# fr5949_v3.net
KiCad netlist of a schematic drawn in EAGLE
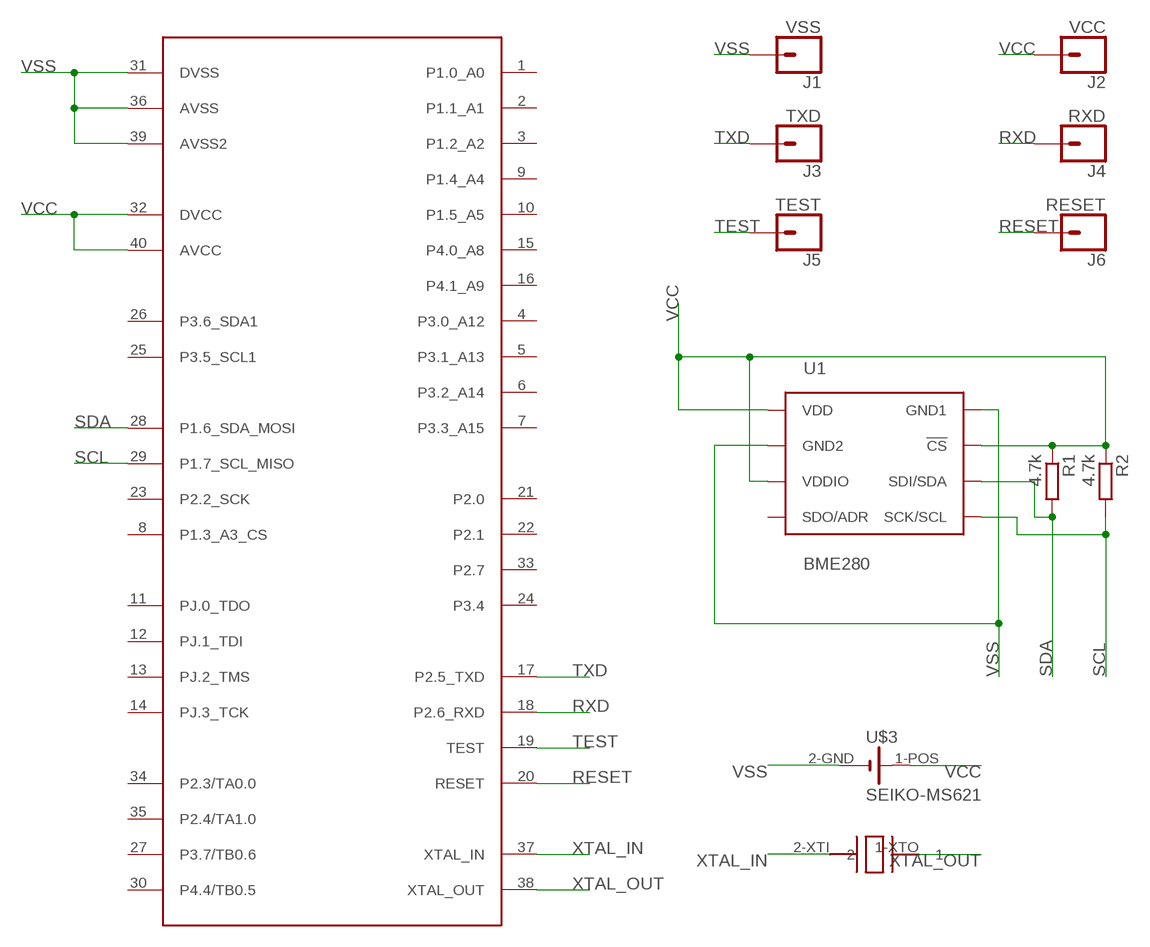
[diagram p0: schematic, sheet 1]

(export (version "E")
  (design (tool "Eeschema 10.0.6"))
  (components
    (comp (ref "J1")
      (value "VSS")
      (footprint "eagle-import:1X01")
      (libsource (lib "eagle-import") (part "CONN_01"))
    )
    (comp (ref "J2")
      (value "VCC")
      (footprint "eagle-import:1X01")
      (libsource (lib "eagle-import") (part "CONN_01"))
    )
    (comp (ref "J3")
      (value "TXD")
      (footprint "eagle-import:1X01")
      (libsource (lib "eagle-import") (part "CONN_01"))
    )
    (comp (ref "J4")
      (value "RXD")
      (footprint "eagle-import:1X01")
      (libsource (lib "eagle-import") (part "CONN_01"))
    )
    (comp (ref "J5")
      (value "TEST")
      (footprint "eagle-import:1X01")
      (libsource (lib "eagle-import") (part "CONN_01"))
    )
    (comp (ref "J6")
      (value "RESET")
      (footprint "eagle-import:1X01")
      (libsource (lib "eagle-import") (part "CONN_01"))
    )
    (comp (ref "R1")
      (value "4.7k")
      (footprint "eagle-import:R0201")
      (libsource (lib "eagle-import") (part "R-EU_R0201"))
    )
    (comp (ref "R2")
      (value "4.7k")
      (footprint "eagle-import:R0201")
      (libsource (lib "eagle-import") (part "R-EU_R0201"))
    )
    (comp (ref "U$1")
      (value "MSP430FR5949_RHA")
      (footprint "eagle-import:RHA-40-VQFN")
      (libsource (lib "eagle-import") (part "MSP430FR5949_RHA"))
    )
    (comp (ref "U$2")
      (value "ABS06")
      (footprint "eagle-import:2.0X1.0RTC")
      (libsource (lib "eagle-import") (part "ABS06"))
    )
    (comp (ref "U$3")
      (value "SEIKO-MS621")
      (footprint "eagle-import:SEIKO_MICRO")
      (libsource (lib "eagle-import") (part "SEIKO-MS621"))
    )
    (comp (ref "U1")
      (value "BME280")
      (footprint "eagle-import:BME280_LGA")
      (libsource (lib "eagle-import") (part "BME280"))
    )
  )
  (nets
    (net (code "1") (name "/RESET") (class "Default")
      (node (ref "J6") (pin "1") (pinfunction "1_1") (pintype "passive"))
      (node (ref "U$1") (pin "20") (pinfunction "RESET_20") (pintype "bidirectional"))
    )
    (net (code "2") (name "/RXD") (class "Default")
      (node (ref "J4") (pin "1") (pinfunction "1_1") (pintype "passive"))
      (node (ref "U$1") (pin "18") (pinfunction "P2.6_RXD_18") (pintype "bidirectional"))
    )
    (net (code "3") (name "/SCL") (class "Default")
      (node (ref "R2") (pin "2") (pinfunction "2_2") (pintype "passive"))
      (node (ref "U$1") (pin "29") (pinfunction "P1.7_SCL_MISO_29") (pintype "bidirectional"))
      (node (ref "U1") (pin "P$4") (pinfunction "SCK/SCL_P$4") (pintype "bidirectional"))
    )
    (net (code "4") (name "/SDA") (class "Default")
      (node (ref "R1") (pin "2") (pinfunction "2_2") (pintype "passive"))
      (node (ref "U$1") (pin "28") (pinfunction "P1.6_SDA_MOSI_28") (pintype "bidirectional"))
      (node (ref "U1") (pin "P$3") (pinfunction "SDI/SDA_P$3") (pintype "bidirectional"))
    )
    (net (code "5") (name "/TEST") (class "Default")
      (node (ref "J5") (pin "1") (pinfunction "1_1") (pintype "passive"))
      (node (ref "U$1") (pin "19") (pinfunction "TEST_19") (pintype "bidirectional"))
    )
    (net (code "6") (name "/TXD") (class "Default")
      (node (ref "J3") (pin "1") (pinfunction "1_1") (pintype "passive"))
      (node (ref "U$1") (pin "17") (pinfunction "P2.5_TXD_17") (pintype "bidirectional"))
    )
    (net (code "7") (name "/VCC") (class "Default")
      (node (ref "J2") (pin "1") (pinfunction "1_1") (pintype "passive"))
      (node (ref "R1") (pin "1") (pinfunction "1_1") (pintype "passive"))
      (node (ref "R2") (pin "1") (pinfunction "1_1") (pintype "passive"))
      (node (ref "U$1") (pin "32") (pinfunction "DVCC_32") (pintype "bidirectional"))
      (node (ref "U$1") (pin "40") (pinfunction "AVCC_40") (pintype "bidirectional"))
      (node (ref "U$3") (pin "1-POS") (pinfunction "+_1-POS") (pintype "passive"))
      (node (ref "U1") (pin "P$2") (pinfunction "~{CS}_P$2") (pintype "bidirectional"))
      (node (ref "U1") (pin "P$6") (pinfunction "VDDIO_P$6") (pintype "bidirectional"))
      (node (ref "U1") (pin "P$8") (pinfunction "VDD_P$8") (pintype "bidirectional"))
    )
    (net (code "8") (name "/VSS") (class "Default")
      (node (ref "J1") (pin "1") (pinfunction "1_1") (pintype "passive"))
      (node (ref "U$1") (pin "31") (pinfunction "DVSS_31") (pintype "bidirectional"))
      (node (ref "U$1") (pin "36") (pinfunction "AVSS_36") (pintype "bidirectional"))
      (node (ref "U$1") (pin "39") (pinfunction "AVSS2_39") (pintype "bidirectional"))
      (node (ref "U$3") (pin "2-GND") (pinfunction "-_2-GND") (pintype "passive"))
      (node (ref "U1") (pin "P$1") (pinfunction "GND1_P$1") (pintype "bidirectional"))
      (node (ref "U1") (pin "P$7") (pinfunction "GND2_P$7") (pintype "bidirectional"))
    )
    (net (code "9") (name "/XTAL_IN") (class "Default")
      (node (ref "U$1") (pin "37") (pinfunction "XTAL_IN_37") (pintype "bidirectional"))
      (node (ref "U$2") (pin "2-XTI") (pinfunction "2_2-XTI") (pintype "bidirectional"))
    )
    (net (code "10") (name "/XTAL_OUT") (class "Default")
      (node (ref "U$1") (pin "38") (pinfunction "XTAL_OUT_38") (pintype "bidirectional"))
      (node (ref "U$2") (pin "1-XTO") (pinfunction "1_1-XTO") (pintype "bidirectional"))
    )
    (net (code "11") (name "unconnected-(U$1-P1.0_A0-Pad1)") (class "Default")
      (node (ref "U$1") (pin "1") (pinfunction "P1.0_A0_1") (pintype "bidirectional"))
    )
    (net (code "12") (name "unconnected-(U$1-P1.1_A1-Pad2)") (class "Default")
      (node (ref "U$1") (pin "2") (pinfunction "P1.1_A1_2") (pintype "bidirectional"))
    )
    (net (code "13") (name "unconnected-(U$1-P1.2_A2-Pad3)") (class "Default")
      (node (ref "U$1") (pin "3") (pinfunction "P1.2_A2_3") (pintype "bidirectional"))
    )
    (net (code "14") (name "unconnected-(U$1-P1.3_A3_CS-Pad8)") (class "Default")
      (node (ref "U$1") (pin "8") (pinfunction "P1.3_A3_CS_8") (pintype "bidirectional"))
    )
    (net (code "15") (name "unconnected-(U$1-P1.4_A4-Pad9)") (class "Default")
      (node (ref "U$1") (pin "9") (pinfunction "P1.4_A4_9") (pintype "bidirectional"))
    )
    (net (code "16") (name "unconnected-(U$1-P1.5_A5-Pad10)") (class "Default")
      (node (ref "U$1") (pin "10") (pinfunction "P1.5_A5_10") (pintype "bidirectional"))
    )
    (net (code "17") (name "unconnected-(U$1-P2.0-Pad21)") (class "Default")
      (node (ref "U$1") (pin "21") (pinfunction "P2.0_21") (pintype "bidirectional"))
    )
    (net (code "18") (name "unconnected-(U$1-P2.1-Pad22)") (class "Default")
      (node (ref "U$1") (pin "22") (pinfunction "P2.1_22") (pintype "bidirectional"))
    )
    (net (code "19") (name "unconnected-(U$1-P2.2_SCK-Pad23)") (class "Default")
      (node (ref "U$1") (pin "23") (pinfunction "P2.2_SCK_23") (pintype "bidirectional"))
    )
    (net (code "20") (name "unconnected-(U$1-P2.3{slash}TA0.0-Pad34)") (class "Default")
      (node (ref "U$1") (pin "34") (pinfunction "P2.3/TA0.0_34") (pintype "bidirectional"))
    )
    (net (code "21") (name "unconnected-(U$1-P2.4{slash}TA1.0-Pad35)") (class "Default")
      (node (ref "U$1") (pin "35") (pinfunction "P2.4/TA1.0_35") (pintype "bidirectional"))
    )
    (net (code "22") (name "unconnected-(U$1-P2.7-Pad33)") (class "Default")
      (node (ref "U$1") (pin "33") (pinfunction "P2.7_33") (pintype "bidirectional"))
    )
    (net (code "23") (name "unconnected-(U$1-P3.0_A12-Pad4)") (class "Default")
      (node (ref "U$1") (pin "4") (pinfunction "P3.0_A12_4") (pintype "bidirectional"))
    )
    (net (code "24") (name "unconnected-(U$1-P3.1_A13-Pad5)") (class "Default")
      (node (ref "U$1") (pin "5") (pinfunction "P3.1_A13_5") (pintype "bidirectional"))
    )
    (net (code "25") (name "unconnected-(U$1-P3.2_A14-Pad6)") (class "Default")
      (node (ref "U$1") (pin "6") (pinfunction "P3.2_A14_6") (pintype "bidirectional"))
    )
    (net (code "26") (name "unconnected-(U$1-P3.3_A15-Pad7)") (class "Default")
      (node (ref "U$1") (pin "7") (pinfunction "P3.3_A15_7") (pintype "bidirectional"))
    )
    (net (code "27") (name "unconnected-(U$1-P3.4-Pad24)") (class "Default")
      (node (ref "U$1") (pin "24") (pinfunction "P3.4_24") (pintype "bidirectional"))
    )
    (net (code "28") (name "unconnected-(U$1-P3.5_SCL1-Pad25)") (class "Default")
      (node (ref "U$1") (pin "25") (pinfunction "P3.5_SCL1_25") (pintype "bidirectional"))
    )
    (net (code "29") (name "unconnected-(U$1-P3.6_SDA1-Pad26)") (class "Default")
      (node (ref "U$1") (pin "26") (pinfunction "P3.6_SDA1_26") (pintype "bidirectional"))
    )
    (net (code "30") (name "unconnected-(U$1-P3.7{slash}TB0.6-Pad27)") (class "Default")
      (node (ref "U$1") (pin "27") (pinfunction "P3.7/TB0.6_27") (pintype "bidirectional"))
    )
    (net (code "31") (name "unconnected-(U$1-P4.0_A8-Pad15)") (class "Default")
      (node (ref "U$1") (pin "15") (pinfunction "P4.0_A8_15") (pintype "bidirectional"))
    )
    (net (code "32") (name "unconnected-(U$1-P4.1_A9-Pad16)") (class "Default")
      (node (ref "U$1") (pin "16") (pinfunction "P4.1_A9_16") (pintype "bidirectional"))
    )
    (net (code "33") (name "unconnected-(U$1-P4.4{slash}TB0.5-Pad30)") (class "Default")
      (node (ref "U$1") (pin "30") (pinfunction "P4.4/TB0.5_30") (pintype "bidirectional"))
    )
    (net (code "34") (name "unconnected-(U$1-PJ.0_TDO-Pad11)") (class "Default")
      (node (ref "U$1") (pin "11") (pinfunction "PJ.0_TDO_11") (pintype "bidirectional"))
    )
    (net (code "35") (name "unconnected-(U$1-PJ.1_TDI-Pad12)") (class "Default")
      (node (ref "U$1") (pin "12") (pinfunction "PJ.1_TDI_12") (pintype "bidirectional"))
    )
    (net (code "36") (name "unconnected-(U$1-PJ.2_TMS-Pad13)") (class "Default")
      (node (ref "U$1") (pin "13") (pinfunction "PJ.2_TMS_13") (pintype "bidirectional"))
    )
    (net (code "37") (name "unconnected-(U$1-PJ.3_TCK-Pad14)") (class "Default")
      (node (ref "U$1") (pin "14") (pinfunction "PJ.3_TCK_14") (pintype "bidirectional"))
    )
    (net (code "38") (name "unconnected-(U1-SDO{slash}ADR-PadP$5)") (class "Default")
      (node (ref "U1") (pin "P$5") (pinfunction "SDO/ADR_P$5") (pintype "bidirectional"))
    )
  )
)
